# Output.net
KiCad netlist of a schematic drawn in Altium Designer
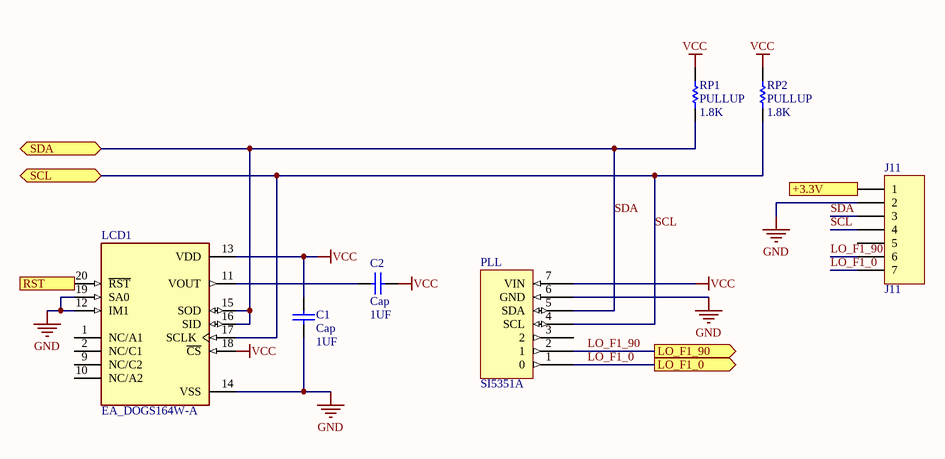
[diagram p0: Output.SchDoc]

(export (version "E")
  (design (tool "Eeschema 10.0.6"))
  (components
    (comp (ref "C1")
      (value "Cap")
      (footprint "RADIAL-0.1")
      (description "Capacitor")
      (fields
        (field (name "MANUFACTURER PART NUMBER") "ESE105M100AC3EA")
        (field (name "ALTIUM_VALUE") "1UF")
        (field (name "PUBLISHER") "Altium Limited")
      )
      (libsource (lib "ECE295-Capacitors-TH") (part "CAP ALUM 1UF 20% 100V RADIAL"))
    )
    (comp (ref "C2")
      (value "Cap")
      (footprint "RADIAL-0.1")
      (description "Capacitor")
      (fields
        (field (name "MANUFACTURER PART NUMBER") "ESE105M100AC3EA")
        (field (name "ALTIUM_VALUE") "1UF")
        (field (name "PUBLISHER") "Altium Limited")
      )
      (libsource (lib "ECE295-Capacitors-TH") (part "CAP ALUM 1UF 20% 100V RADIAL"))
    )
    (comp (ref "J11")
      (value "J11")
      (footprint "HDR1X7")
      (description "Header, 7-Pin")
      (fields (field (name "PUBLISHER") "Altium Limited"))
      (libsource (lib "Miscellaneous Connectors") (part "Header 7"))
    )
    (comp (ref "LCD1")
      (value "EA_DOGS164W-A")
      (footprint "LCD_EA_DOGS164W-A")
      (fields (field (name "MF") "Display Visions") (field (name "MP") "EA DOGS164W-A"))
      (libsource (lib "EA_DOGS164W-A") (part "EA_DOGS164W-A"))
    )
    (comp (ref "PLL") (value "SI5351A") (libsource (lib "adafruit_2045") (part "SI5351A")))
    (comp (ref "RP1")
      (value "PULLUP")
      (footprint "AXIAL-0.1-RES")
      (description "Resistor")
      (fields
        (field (name "ALTIUM_VALUE") "1.8K")
        (field (name "MANUFACTURER PART NUMBER") "CFR-25JB-52-1K8")
        (field (name "TOLERANCE") "0.05")
        (field (name "PUBLISHER") "Altium Limited")
      )
      (libsource (lib "ECE295-Resistors-TH") (part "RES 1.8K OHM 5% 1/4W AXIAL"))
    )
    (comp (ref "RP2")
      (value "PULLUP")
      (footprint "AXIAL-0.1-RES")
      (description "Resistor")
      (fields
        (field (name "ALTIUM_VALUE") "1.8K")
        (field (name "MANUFACTURER PART NUMBER") "CFR-25JB-52-1K8")
        (field (name "TOLERANCE") "0.05")
        (field (name "PUBLISHER") "Altium Limited")
      )
      (libsource (lib "ECE295-Resistors-TH") (part "RES 1.8K OHM 5% 1/4W AXIAL"))
    )
  )
  (nets
    (net (code "1") (name "/+3.3V") (class "Default")
      (node (ref "J11") (pin "1") (pinfunction "1_1") (pintype "passive"))
    )
    (net (code "2") (name "/LO_F1_0") (class "Default")
      (node (ref "J11") (pin "7") (pinfunction "7_7") (pintype "passive"))
      (node (ref "PLL") (pin "1") (pinfunction "0_1") (pintype "output"))
    )
    (net (code "3") (name "/LO_F1_90") (class "Default")
      (node (ref "J11") (pin "6") (pinfunction "6_6") (pintype "passive"))
      (node (ref "PLL") (pin "2") (pinfunction "1_2") (pintype "output"))
    )
    (net (code "4") (name "/RST") (class "Default")
      (node (ref "LCD1") (pin "20") (pinfunction "~{RST}_20") (pintype "input"))
    )
    (net (code "5") (name "/SCL") (class "Default")
      (node (ref "J11") (pin "4") (pinfunction "4_4") (pintype "passive"))
      (node (ref "LCD1") (pin "17") (pinfunction "SCLK_17") (pintype "input"))
      (node (ref "PLL") (pin "4") (pinfunction "SCL_4") (pintype "bidirectional"))
      (node (ref "RP2") (pin "1") (pinfunction "1_1") (pintype "passive"))
    )
    (net (code "6") (name "/SDA") (class "Default")
      (node (ref "J11") (pin "3") (pinfunction "3_3") (pintype "passive"))
      (node (ref "LCD1") (pin "15") (pinfunction "SOD_15") (pintype "bidirectional"))
      (node (ref "LCD1") (pin "16") (pinfunction "SID_16") (pintype "bidirectional"))
      (node (ref "PLL") (pin "5") (pinfunction "SDA_5") (pintype "bidirectional"))
      (node (ref "RP1") (pin "1") (pinfunction "1_1") (pintype "passive"))
    )
    (net (code "7") (name "GND") (class "Default")
      (node (ref "C1") (pin "1") (pinfunction "1_1") (pintype "passive"))
      (node (ref "J11") (pin "2") (pinfunction "2_2") (pintype "passive"))
      (node (ref "LCD1") (pin "12") (pinfunction "IM1_12") (pintype "input"))
      (node (ref "LCD1") (pin "14") (pinfunction "VSS_14") (pintype "power_in"))
      (node (ref "LCD1") (pin "19") (pinfunction "SA0_19") (pintype "input"))
      (node (ref "PLL") (pin "6") (pinfunction "GND_6") (pintype "input"))
    )
    (net (code "8") (name "Net-(LCD1-VOUT)") (class "Default")
      (node (ref "C2") (pin "2") (pinfunction "2_2") (pintype "passive"))
      (node (ref "LCD1") (pin "11") (pinfunction "VOUT_11") (pintype "output"))
    )
    (net (code "9") (name "VCC") (class "Default")
      (node (ref "C1") (pin "2") (pinfunction "2_2") (pintype "passive"))
      (node (ref "C2") (pin "1") (pinfunction "1_1") (pintype "passive"))
      (node (ref "LCD1") (pin "13") (pinfunction "VDD_13") (pintype "power_in"))
      (node (ref "LCD1") (pin "18") (pinfunction "~{CS}_18") (pintype "input"))
      (node (ref "PLL") (pin "7") (pinfunction "VIN_7") (pintype "input"))
      (node (ref "RP1") (pin "2") (pinfunction "2_2") (pintype "passive"))
      (node (ref "RP2") (pin "2") (pinfunction "2_2") (pintype "passive"))
    )
    (net (code "10") (name "unconnected-(J11-Pad5)") (class "Default")
      (node (ref "J11") (pin "5") (pinfunction "5_5") (pintype "passive"))
    )
    (net (code "11") (name "unconnected-(LCD1-NC{slash}A1-Pad1)") (class "Default")
      (node (ref "LCD1") (pin "1") (pinfunction "NC/A1_1") (pintype "passive"))
    )
    (net (code "12") (name "unconnected-(LCD1-NC{slash}A2-Pad10)") (class "Default")
      (node (ref "LCD1") (pin "10") (pinfunction "NC/A2_10") (pintype "passive"))
    )
    (net (code "13") (name "unconnected-(LCD1-NC{slash}C1-Pad2)") (class "Default")
      (node (ref "LCD1") (pin "2") (pinfunction "NC/C1_2") (pintype "passive"))
    )
    (net (code "14") (name "unconnected-(LCD1-NC{slash}C2-Pad9)") (class "Default")
      (node (ref "LCD1") (pin "9") (pinfunction "NC/C2_9") (pintype "passive"))
    )
    (net (code "15") (name "unconnected-(PLL-2-Pad3)") (class "Default")
      (node (ref "PLL") (pin "3") (pinfunction "2_3") (pintype "output"))
    )
  )
)
